# L6205_2XDC.net
KiCad netlist of a schematic drawn in EAGLE
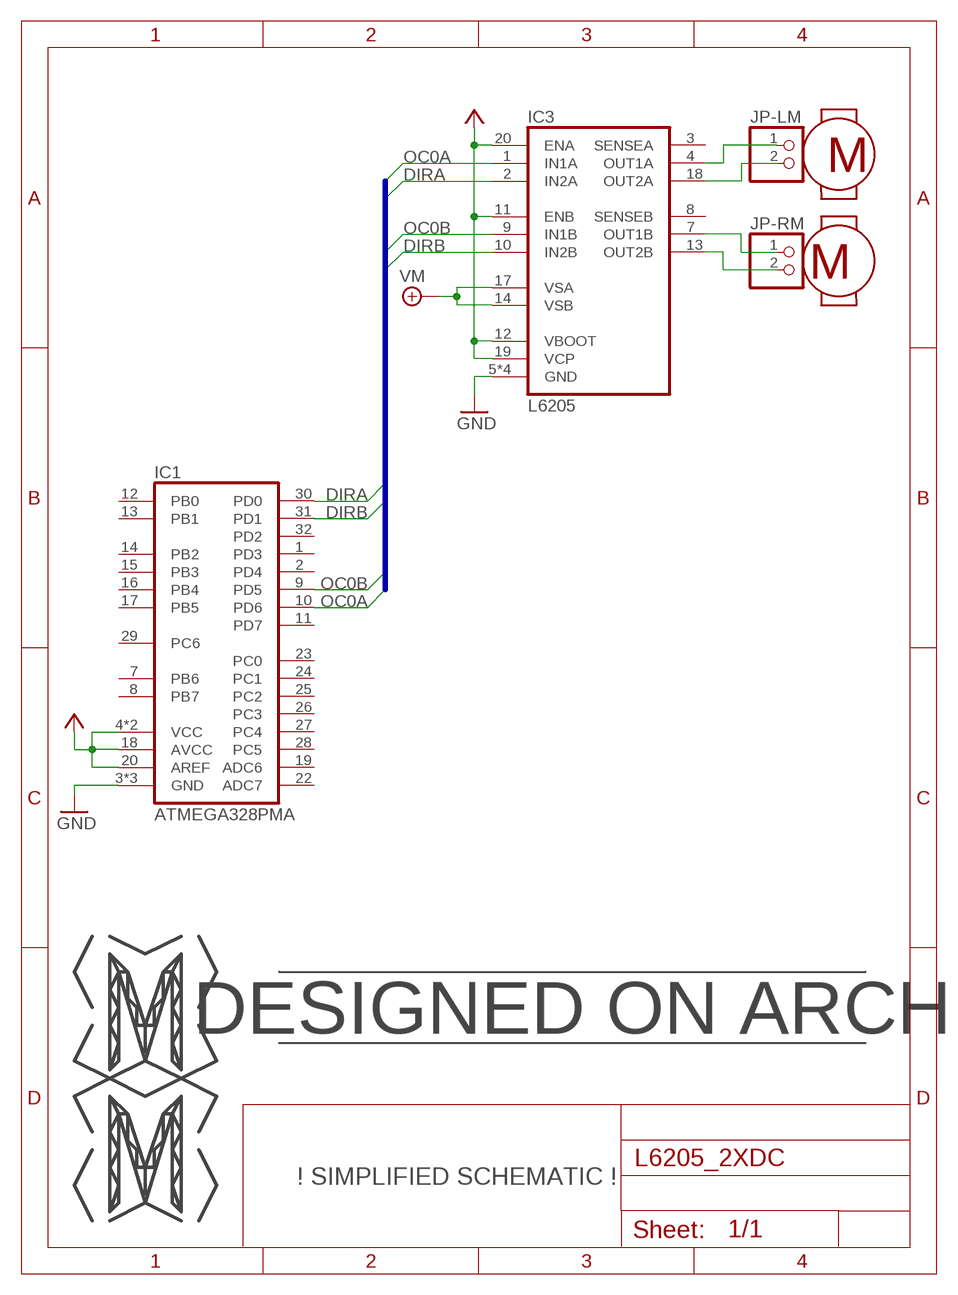
[diagram p0: schematic, sheet 1]

(export (version "E")
  (design (tool "Eeschema 10.0.6"))
  (components
    (comp (ref "IC1")
      (value "ATMEGA328PMA")
      (footprint "eagle-import:TQFP32")
      (libsource (lib "eagle-import") (part "ATMEGA328PMA"))
    )
    (comp (ref "IC3")
      (value "L6205")
      (footprint "eagle-import:SO20")
      (libsource (lib "eagle-import") (part "L6205"))
    )
    (comp (ref "JP-LM")
      (value "PINHD-1X2")
      (footprint "eagle-import:1X02")
      (libsource (lib "eagle-import") (part "PINHD-1X2"))
    )
    (comp (ref "JP-RM")
      (value "PINHD-1X2")
      (footprint "eagle-import:1X02")
      (libsource (lib "eagle-import") (part "PINHD-1X2"))
    )
  )
  (nets
    (net (code "1") (name "/DIRA") (class "Default")
      (node (ref "IC1") (pin "30") (pinfunction "PD0_30") (pintype "bidirectional"))
      (node (ref "IC3") (pin "2") (pinfunction "IN2A_2") (pintype "input"))
    )
    (net (code "2") (name "/DIRB") (class "Default")
      (node (ref "IC1") (pin "31") (pinfunction "PD1_31") (pintype "bidirectional"))
      (node (ref "IC3") (pin "10") (pinfunction "IN2B_10") (pintype "input"))
    )
    (net (code "3") (name "/OC0A") (class "Default")
      (node (ref "IC1") (pin "10") (pinfunction "PD6_10") (pintype "bidirectional"))
      (node (ref "IC3") (pin "1") (pinfunction "IN1A_1") (pintype "input"))
    )
    (net (code "4") (name "/OC0B") (class "Default")
      (node (ref "IC1") (pin "9") (pinfunction "PD5_9") (pintype "bidirectional"))
      (node (ref "IC3") (pin "9") (pinfunction "IN1B_9") (pintype "input"))
    )
    (net (code "5") (name "/PB6") (class "Default")
      (node (ref "IC1") (pin "7") (pinfunction "PB6_7") (pintype "power_in"))
    )
    (net (code "6") (name "GND") (class "Default")
      (node (ref "IC1") (pin "21") (pinfunction "GND_21") (pintype "bidirectional"))
      (node (ref "IC1") (pin "3") (pinfunction "GND_3") (pintype "bidirectional"))
      (node (ref "IC1") (pin "5") (pinfunction "GND_5") (pintype "bidirectional"))
      (node (ref "IC3") (pin "15") (pinfunction "GND_15") (pintype "power_in"))
      (node (ref "IC3") (pin "16") (pinfunction "GND_16") (pintype "power_in"))
      (node (ref "IC3") (pin "5") (pinfunction "GND_5") (pintype "power_in"))
      (node (ref "IC3") (pin "6") (pinfunction "GND_6") (pintype "power_in"))
    )
    (net (code "7") (name "Net-(IC3-OUT1A)") (class "Default")
      (node (ref "IC3") (pin "4") (pinfunction "OUT1A_4") (pintype "output"))
      (node (ref "JP-LM") (pin "1") (pinfunction "1_1") (pintype "passive"))
    )
    (net (code "8") (name "Net-(IC3-OUT1B)") (class "Default")
      (node (ref "IC3") (pin "7") (pinfunction "OUT1B_7") (pintype "output"))
      (node (ref "JP-RM") (pin "1") (pinfunction "1_1") (pintype "passive"))
    )
    (net (code "9") (name "Net-(IC3-OUT2A)") (class "Default")
      (node (ref "IC3") (pin "18") (pinfunction "OUT2A_18") (pintype "output"))
      (node (ref "JP-LM") (pin "2") (pinfunction "2_2") (pintype "passive"))
    )
    (net (code "10") (name "Net-(IC3-OUT2B)") (class "Default")
      (node (ref "IC3") (pin "13") (pinfunction "OUT2B_13") (pintype "output"))
      (node (ref "JP-RM") (pin "2") (pinfunction "2_2") (pintype "passive"))
    )
    (net (code "11") (name "VCC") (class "Default")
      (node (ref "IC1") (pin "18") (pinfunction "AVCC_18") (pintype "bidirectional"))
      (node (ref "IC1") (pin "20") (pinfunction "AREF_20") (pintype "bidirectional"))
      (node (ref "IC1") (pin "4") (pinfunction "VCC_4") (pintype "bidirectional"))
      (node (ref "IC1") (pin "6") (pinfunction "VCC_6") (pintype "bidirectional"))
      (node (ref "IC3") (pin "11") (pinfunction "ENB_11") (pintype "input"))
      (node (ref "IC3") (pin "12") (pinfunction "VBOOT_12") (pintype "power_in"))
      (node (ref "IC3") (pin "19") (pinfunction "VCP_19") (pintype "power_in"))
      (node (ref "IC3") (pin "20") (pinfunction "ENA_20") (pintype "input"))
    )
    (net (code "12") (name "VM") (class "Default")
      (node (ref "IC3") (pin "14") (pinfunction "VSB_14") (pintype "power_in"))
      (node (ref "IC3") (pin "17") (pinfunction "VSA_17") (pintype "power_in"))
    )
    (net (code "13") (name "unconnected-(IC1-ADC6-Pad19)") (class "Default")
      (node (ref "IC1") (pin "19") (pinfunction "ADC6_19") (pintype "bidirectional"))
    )
    (net (code "14") (name "unconnected-(IC1-ADC7-Pad22)") (class "Default")
      (node (ref "IC1") (pin "22") (pinfunction "ADC7_22") (pintype "bidirectional"))
    )
    (net (code "15") (name "unconnected-(IC1-PB0-Pad12)") (class "Default")
      (node (ref "IC1") (pin "12") (pinfunction "PB0_12") (pintype "bidirectional"))
    )
    (net (code "16") (name "unconnected-(IC1-PB1-Pad13)") (class "Default")
      (node (ref "IC1") (pin "13") (pinfunction "PB1_13") (pintype "bidirectional"))
    )
    (net (code "17") (name "unconnected-(IC1-PB2-Pad14)") (class "Default")
      (node (ref "IC1") (pin "14") (pinfunction "PB2_14") (pintype "bidirectional"))
    )
    (net (code "18") (name "unconnected-(IC1-PB3-Pad15)") (class "Default")
      (node (ref "IC1") (pin "15") (pinfunction "PB3_15") (pintype "bidirectional"))
    )
    (net (code "19") (name "unconnected-(IC1-PB4-Pad16)") (class "Default")
      (node (ref "IC1") (pin "16") (pinfunction "PB4_16") (pintype "bidirectional"))
    )
    (net (code "20") (name "unconnected-(IC1-PB5-Pad17)") (class "Default")
      (node (ref "IC1") (pin "17") (pinfunction "PB5_17") (pintype "output"))
    )
    (net (code "21") (name "unconnected-(IC1-PB7-Pad8)") (class "Default")
      (node (ref "IC1") (pin "8") (pinfunction "PB7_8") (pintype "input"))
    )
    (net (code "22") (name "unconnected-(IC1-PC0-Pad23)") (class "Default")
      (node (ref "IC1") (pin "23") (pinfunction "PC0_23") (pintype "bidirectional"))
    )
    (net (code "23") (name "unconnected-(IC1-PC1-Pad24)") (class "Default")
      (node (ref "IC1") (pin "24") (pinfunction "PC1_24") (pintype "bidirectional"))
    )
    (net (code "24") (name "unconnected-(IC1-PC2-Pad25)") (class "Default")
      (node (ref "IC1") (pin "25") (pinfunction "PC2_25") (pintype "bidirectional"))
    )
    (net (code "25") (name "unconnected-(IC1-PC3-Pad26)") (class "Default")
      (node (ref "IC1") (pin "26") (pinfunction "PC3_26") (pintype "bidirectional"))
    )
    (net (code "26") (name "unconnected-(IC1-PC4-Pad27)") (class "Default")
      (node (ref "IC1") (pin "27") (pinfunction "PC4_27") (pintype "bidirectional"))
    )
    (net (code "27") (name "unconnected-(IC1-PC5-Pad28)") (class "Default")
      (node (ref "IC1") (pin "28") (pinfunction "PC5_28") (pintype "bidirectional"))
    )
    (net (code "28") (name "unconnected-(IC1-PC6-Pad29)") (class "Default")
      (node (ref "IC1") (pin "29") (pinfunction "PC6_29") (pintype "input"))
    )
    (net (code "29") (name "unconnected-(IC1-PD2-Pad32)") (class "Default")
      (node (ref "IC1") (pin "32") (pinfunction "PD2_32") (pintype "bidirectional"))
    )
    (net (code "30") (name "unconnected-(IC1-PD3-Pad1)") (class "Default")
      (node (ref "IC1") (pin "1") (pinfunction "PD3_1") (pintype "bidirectional"))
    )
    (net (code "31") (name "unconnected-(IC1-PD4-Pad2)") (class "Default")
      (node (ref "IC1") (pin "2") (pinfunction "PD4_2") (pintype "bidirectional"))
    )
    (net (code "32") (name "unconnected-(IC1-PD7-Pad11)") (class "Default")
      (node (ref "IC1") (pin "11") (pinfunction "PD7_11") (pintype "bidirectional"))
    )
    (net (code "33") (name "unconnected-(IC3-SENSEA-Pad3)") (class "Default")
      (node (ref "IC3") (pin "3") (pinfunction "SENSEA_3") (pintype "output"))
    )
    (net (code "34") (name "unconnected-(IC3-SENSEB-Pad8)") (class "Default")
      (node (ref "IC3") (pin "8") (pinfunction "SENSEB_8") (pintype "output"))
    )
  )
)
